# taxi.net
KiCad netlist of a schematic drawn in EAGLE
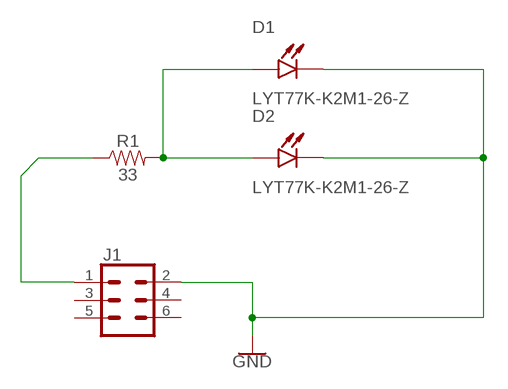
[diagram p0: schematic, sheet 1]

(export (version "E")
  (design (tool "Eeschema 10.0.6"))
  (components
    (comp (ref "D1")
      (value "LYT77K-K2M1-26-Z")
      (footprint "eagle-import:LED_LYT77K-K2M1-26-Z")
      (fields (field (name "MF") "Osram"))
      (libsource (lib "eagle-import") (part "LYT77K-K2M1-26-Z"))
    )
    (comp (ref "D2")
      (value "LYT77K-K2M1-26-Z")
      (footprint "eagle-import:LED_LYT77K-K2M1-26-Z")
      (fields (field (name "MF") "Osram"))
      (libsource (lib "eagle-import") (part "LYT77K-K2M1-26-Z"))
    )
    (comp (ref "J1")
      (value "CONN_03X2SHROUD")
      (footprint "eagle-import:2X3-SHROUDED")
      (libsource (lib "eagle-import") (part "CONN_03X2SHROUD"))
    )
    (comp (ref "R1")
      (value "33")
      (footprint "eagle-import:0603")
      (libsource (lib "eagle-import") (part "33OHM-0603-1/10W-1%"))
    )
  )
  (nets
    (net (code "1") (name "GND") (class "Default")
      (node (ref "D1") (pin "1") (pinfunction "C_1") (pintype "passive"))
      (node (ref "D2") (pin "1") (pinfunction "C_1") (pintype "passive"))
      (node (ref "J1") (pin "2") (pinfunction "2_2") (pintype "bidirectional"))
    )
    (net (code "2") (name "Net-(D1-A)") (class "Default")
      (node (ref "D1") (pin "2") (pinfunction "A_2") (pintype "passive"))
      (node (ref "D2") (pin "2") (pinfunction "A_2") (pintype "passive"))
      (node (ref "R1") (pin "2") (pinfunction "2_2") (pintype "passive"))
    )
    (net (code "3") (name "Net-(J1-Pad1)") (class "Default")
      (node (ref "J1") (pin "1") (pinfunction "1_1") (pintype "bidirectional"))
      (node (ref "R1") (pin "1") (pinfunction "1_1") (pintype "passive"))
    )
    (net (code "4") (name "unconnected-(J1-Pad3)") (class "Default")
      (node (ref "J1") (pin "3") (pinfunction "3_3") (pintype "bidirectional"))
    )
    (net (code "5") (name "unconnected-(J1-Pad4)") (class "Default")
      (node (ref "J1") (pin "4") (pinfunction "4_4") (pintype "bidirectional"))
    )
    (net (code "6") (name "unconnected-(J1-Pad5)") (class "Default")
      (node (ref "J1") (pin "5") (pinfunction "5_5") (pintype "bidirectional"))
    )
    (net (code "7") (name "unconnected-(J1-Pad6)") (class "Default")
      (node (ref "J1") (pin "6") (pinfunction "6_6") (pintype "bidirectional"))
    )
  )
)
